# Shield.net
KiCad netlist of a schematic drawn in EAGLE
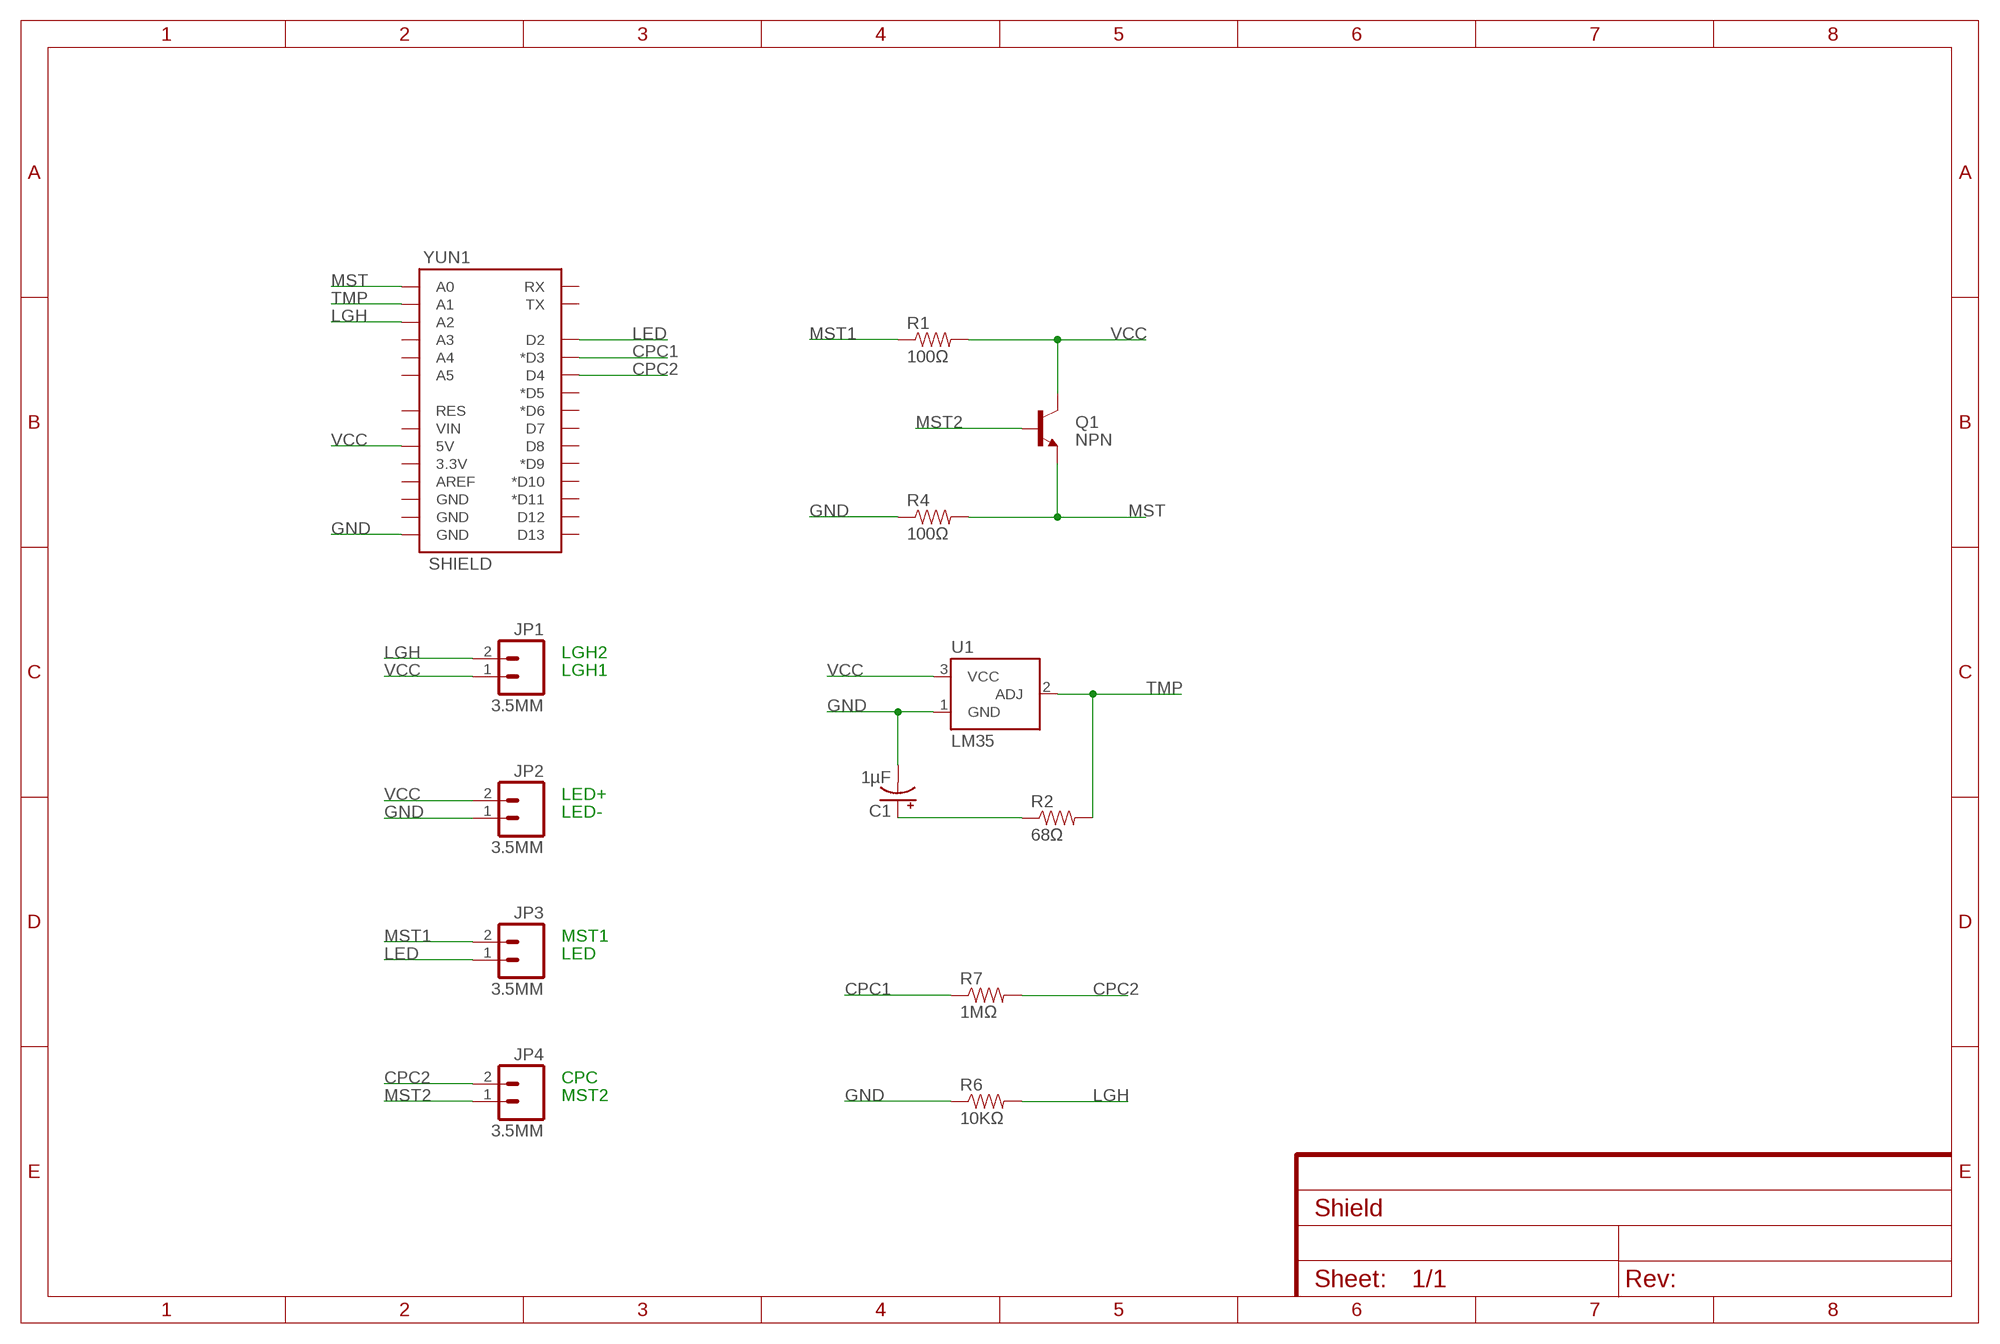
[diagram p0: schematic, sheet 1]

(export (version "E")
  (design (tool "Eeschema 10.0.6"))
  (components
    (comp (ref "C1")
      (value "1µF")
      (footprint "eagle-import:CPOL-RADIAL-100UF-25V")
      (libsource (lib "eagle-import") (part "CAP_POLPTH1"))
    )
    (comp (ref "JP1")
      (value "3.5MM")
      (footprint "eagle-import:SCREWTERMINAL-3.5MM-2")
      (libsource (lib "eagle-import") (part "M023.5MM"))
    )
    (comp (ref "JP2")
      (value "3.5MM")
      (footprint "eagle-import:SCREWTERMINAL-3.5MM-2")
      (libsource (lib "eagle-import") (part "M023.5MM"))
    )
    (comp (ref "JP3")
      (value "3.5MM")
      (footprint "eagle-import:SCREWTERMINAL-3.5MM-2")
      (libsource (lib "eagle-import") (part "M023.5MM"))
    )
    (comp (ref "JP4")
      (value "3.5MM")
      (footprint "eagle-import:SCREWTERMINAL-3.5MM-2")
      (libsource (lib "eagle-import") (part "M023.5MM"))
    )
    (comp (ref "Q1")
      (value "NPN")
      (footprint "eagle-import:TO-92-AMMO")
      (libsource (lib "eagle-import") (part "TRANSISTOR_NPNBC547"))
    )
    (comp (ref "R1")
      (value "100Ω")
      (footprint "eagle-import:AXIAL-0.3")
      (libsource (lib "eagle-import") (part "RESISTORAXIAL-0.3"))
    )
    (comp (ref "R2")
      (value "68Ω")
      (footprint "eagle-import:AXIAL-0.3")
      (libsource (lib "eagle-import") (part "RESISTORAXIAL-0.3"))
    )
    (comp (ref "R4")
      (value "100Ω")
      (footprint "eagle-import:AXIAL-0.3")
      (libsource (lib "eagle-import") (part "RESISTORAXIAL-0.3"))
    )
    (comp (ref "R6")
      (value "10KΩ")
      (footprint "eagle-import:AXIAL-0.3")
      (libsource (lib "eagle-import") (part "RESISTORAXIAL-0.3"))
    )
    (comp (ref "R7")
      (value "1MΩ")
      (footprint "eagle-import:AXIAL-0.3")
      (libsource (lib "eagle-import") (part "RESISTORAXIAL-0.3"))
    )
    (comp (ref "U1")
      (value "LM35")
      (footprint "eagle-import:TO-92")
      (libsource (lib "eagle-import") (part "TEMPERATURE-SENSOR"))
    )
    (comp (ref "YUN1")
      (value "SHIELD")
      (footprint "eagle-import:DUEMILANOVE_VIAS")
      (libsource (lib "eagle-import") (part "ARDUINO_SHIELDNO_SILK"))
    )
  )
  (nets
    (net (code "1") (name "/CPC1") (class "Default")
      (node (ref "R7") (pin "P$1") (pinfunction "1_P$1") (pintype "passive"))
      (node (ref "YUN1") (pin "D3") (pinfunction "*D3_D3") (pintype "bidirectional"))
    )
    (net (code "2") (name "/CPC2") (class "Default")
      (node (ref "JP4") (pin "2") (pinfunction "2_2") (pintype "passive"))
      (node (ref "R7") (pin "P$2") (pinfunction "2_P$2") (pintype "passive"))
      (node (ref "YUN1") (pin "D4") (pinfunction "D4_D4") (pintype "bidirectional"))
    )
    (net (code "3") (name "/GND") (class "Default")
      (node (ref "C1") (pin "2") (pinfunction "-_2") (pintype "passive"))
      (node (ref "JP2") (pin "1") (pinfunction "1_1") (pintype "passive"))
      (node (ref "R4") (pin "P$1") (pinfunction "1_P$1") (pintype "passive"))
      (node (ref "R6") (pin "P$1") (pinfunction "1_P$1") (pintype "passive"))
      (node (ref "U1") (pin "1") (pinfunction "GND_1") (pintype "bidirectional"))
      (node (ref "YUN1") (pin "GND@0") (pinfunction "GND_GND@0") (pintype "bidirectional"))
    )
    (net (code "4") (name "/LED") (class "Default")
      (node (ref "JP3") (pin "1") (pinfunction "1_1") (pintype "passive"))
      (node (ref "YUN1") (pin "D2") (pinfunction "D2_D2") (pintype "bidirectional"))
    )
    (net (code "5") (name "/LGH") (class "Default")
      (node (ref "JP1") (pin "2") (pinfunction "2_2") (pintype "passive"))
      (node (ref "R6") (pin "P$2") (pinfunction "2_P$2") (pintype "passive"))
      (node (ref "YUN1") (pin "A2") (pinfunction "A2_A2") (pintype "bidirectional"))
    )
    (net (code "6") (name "/MST") (class "Default")
      (node (ref "Q1") (pin "3") (pinfunction "E_3") (pintype "passive"))
      (node (ref "R4") (pin "P$2") (pinfunction "2_P$2") (pintype "passive"))
      (node (ref "YUN1") (pin "A0") (pinfunction "A0_A0") (pintype "bidirectional"))
    )
    (net (code "7") (name "/MST1") (class "Default")
      (node (ref "JP3") (pin "2") (pinfunction "2_2") (pintype "passive"))
      (node (ref "R1") (pin "P$1") (pinfunction "1_P$1") (pintype "passive"))
    )
    (net (code "8") (name "/MST2") (class "Default")
      (node (ref "JP4") (pin "1") (pinfunction "1_1") (pintype "passive"))
      (node (ref "Q1") (pin "2") (pinfunction "B_2") (pintype "passive"))
    )
    (net (code "9") (name "/TMP") (class "Default")
      (node (ref "R2") (pin "P$2") (pinfunction "2_P$2") (pintype "passive"))
      (node (ref "U1") (pin "2") (pinfunction "ADJ_2") (pintype "bidirectional"))
      (node (ref "YUN1") (pin "A1") (pinfunction "A1_A1") (pintype "bidirectional"))
    )
    (net (code "10") (name "/VCC") (class "Default")
      (node (ref "JP1") (pin "1") (pinfunction "1_1") (pintype "passive"))
      (node (ref "JP2") (pin "2") (pinfunction "2_2") (pintype "passive"))
      (node (ref "Q1") (pin "1") (pinfunction "C_1") (pintype "passive"))
      (node (ref "R1") (pin "P$2") (pinfunction "2_P$2") (pintype "passive"))
      (node (ref "U1") (pin "3") (pinfunction "VCC_3") (pintype "bidirectional"))
      (node (ref "YUN1") (pin "5V") (pinfunction "5V_5V") (pintype "bidirectional"))
    )
    (net (code "11") (name "Net-(C1-+)") (class "Default")
      (node (ref "C1") (pin "1") (pinfunction "+_1") (pintype "passive"))
      (node (ref "R2") (pin "P$1") (pinfunction "1_P$1") (pintype "passive"))
    )
    (net (code "12") (name "unconnected-(YUN1-*D5-PadD5)") (class "Default")
      (node (ref "YUN1") (pin "D5") (pinfunction "*D5_D5") (pintype "bidirectional"))
    )
    (net (code "13") (name "unconnected-(YUN1-*D6-PadD6)") (class "Default")
      (node (ref "YUN1") (pin "D6") (pinfunction "*D6_D6") (pintype "bidirectional"))
    )
    (net (code "14") (name "unconnected-(YUN1-*D9-PadD9)") (class "Default")
      (node (ref "YUN1") (pin "D9") (pinfunction "*D9_D9") (pintype "bidirectional"))
    )
    (net (code "15") (name "unconnected-(YUN1-*D10-PadD10)") (class "Default")
      (node (ref "YUN1") (pin "D10") (pinfunction "*D10_D10") (pintype "bidirectional"))
    )
    (net (code "16") (name "unconnected-(YUN1-*D11-PadD11)") (class "Default")
      (node (ref "YUN1") (pin "D11") (pinfunction "*D11_D11") (pintype "bidirectional"))
    )
    (net (code "17") (name "unconnected-(YUN1-GND-PadGND@1)") (class "Default")
      (node (ref "YUN1") (pin "GND@1") (pinfunction "GND_GND@1") (pintype "bidirectional"))
    )
    (net (code "18") (name "unconnected-(YUN1-GND-PadGND@2)") (class "Default")
      (node (ref "YUN1") (pin "GND@2") (pinfunction "GND_GND@2") (pintype "bidirectional"))
    )
    (net (code "19") (name "unconnected-(YUN1-Pad3.3V)") (class "Default")
      (node (ref "YUN1") (pin "3.3V") (pinfunction "3.3V_3.3V") (pintype "bidirectional"))
    )
    (net (code "20") (name "unconnected-(YUN1-PadA3)") (class "Default")
      (node (ref "YUN1") (pin "A3") (pinfunction "A3_A3") (pintype "bidirectional"))
    )
    (net (code "21") (name "unconnected-(YUN1-PadA4)") (class "Default")
      (node (ref "YUN1") (pin "A4") (pinfunction "A4_A4") (pintype "bidirectional"))
    )
    (net (code "22") (name "unconnected-(YUN1-PadA5)") (class "Default")
      (node (ref "YUN1") (pin "A5") (pinfunction "A5_A5") (pintype "bidirectional"))
    )
    (net (code "23") (name "unconnected-(YUN1-PadAREF)") (class "Default")
      (node (ref "YUN1") (pin "AREF") (pinfunction "AREF_AREF") (pintype "bidirectional"))
    )
    (net (code "24") (name "unconnected-(YUN1-PadD7)") (class "Default")
      (node (ref "YUN1") (pin "D7") (pinfunction "D7_D7") (pintype "bidirectional"))
    )
    (net (code "25") (name "unconnected-(YUN1-PadD8)") (class "Default")
      (node (ref "YUN1") (pin "D8") (pinfunction "D8_D8") (pintype "bidirectional"))
    )
    (net (code "26") (name "unconnected-(YUN1-PadD12)") (class "Default")
      (node (ref "YUN1") (pin "D12") (pinfunction "D12_D12") (pintype "bidirectional"))
    )
    (net (code "27") (name "unconnected-(YUN1-PadD13)") (class "Default")
      (node (ref "YUN1") (pin "D13") (pinfunction "D13_D13") (pintype "bidirectional"))
    )
    (net (code "28") (name "unconnected-(YUN1-PadRES)") (class "Default")
      (node (ref "YUN1") (pin "RES") (pinfunction "RES_RES") (pintype "bidirectional"))
    )
    (net (code "29") (name "unconnected-(YUN1-PadRX)") (class "Default")
      (node (ref "YUN1") (pin "RX") (pinfunction "RX_RX") (pintype "bidirectional"))
    )
    (net (code "30") (name "unconnected-(YUN1-PadTX)") (class "Default")
      (node (ref "YUN1") (pin "TX") (pinfunction "TX_TX") (pintype "bidirectional"))
    )
    (net (code "31") (name "unconnected-(YUN1-PadVIN)") (class "Default")
      (node (ref "YUN1") (pin "VIN") (pinfunction "VIN_VIN") (pintype "bidirectional"))
    )
  )
)
